# STM32.net
KiCad netlist of a schematic drawn in Altium Designer
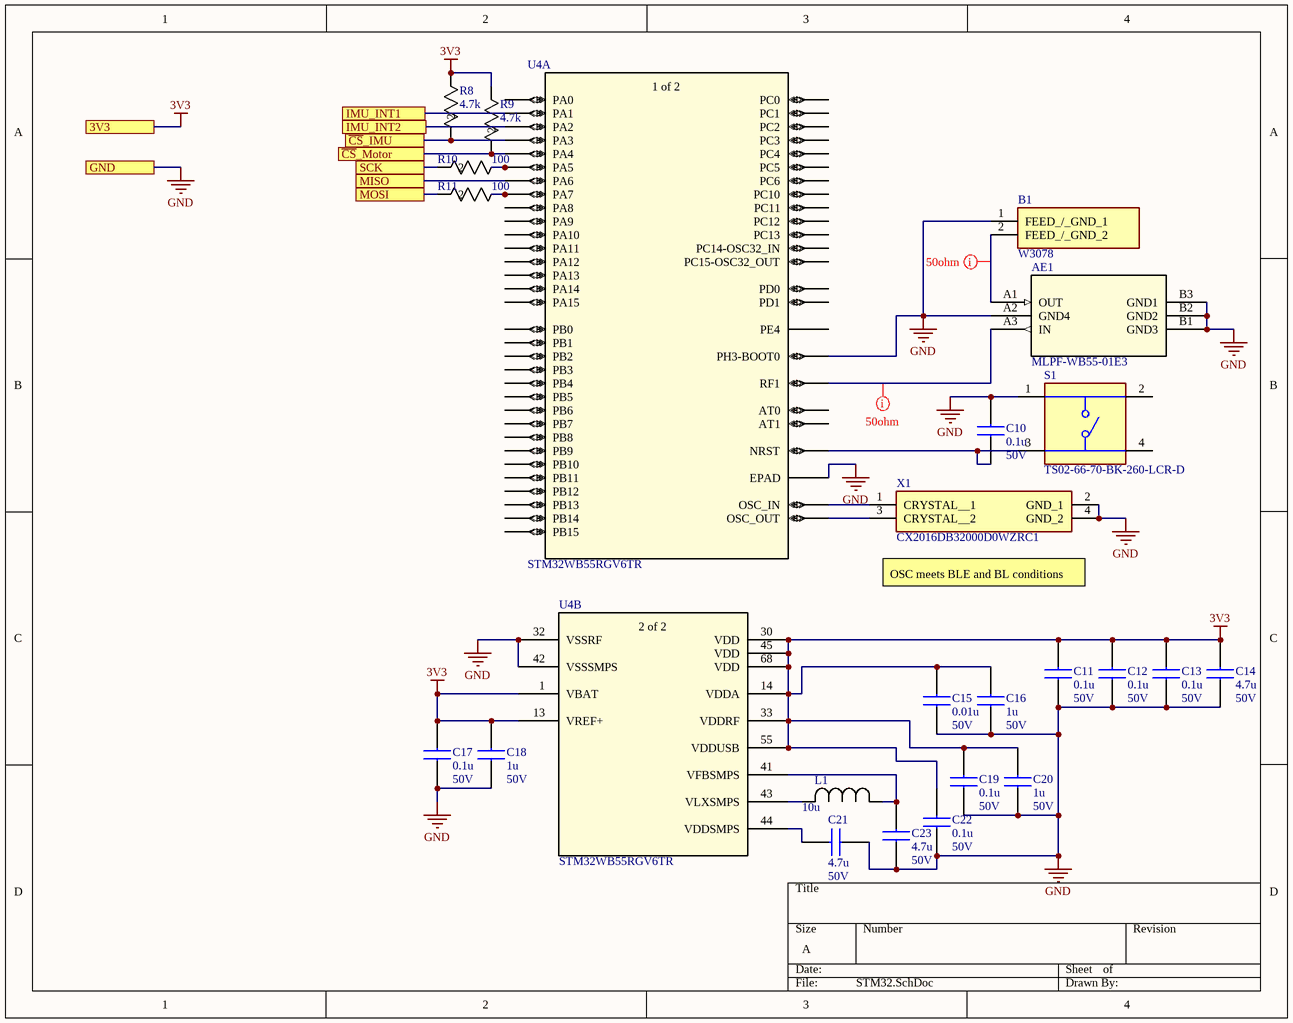
[diagram p0: STM32.SchDoc]

(export (version "E")
  (design (tool "Eeschema 10.0.6"))
  (components
    (comp (ref "AE1")
      (value "MLPF-WB55-01E3")
      (footprint "MLPF-WB55-01E3_STM")
      (description "2.4 GHz Matched filter companion chip for STM32WB55Cx and STM32WB55Rx")
      (fields (field (name "COPYRIGHT") "Copyright (C) 2025 Ultra Librarian. All rights reserved."))
      (libsource (lib "MLPF-WB55-01E3") (part "MLPF-WB55-01E3"))
    )
    (comp (ref "B1")
      (value "W3078")
      (footprint "W3078")
      (description "Antennas CERAMIC W3078 GC380H N")
      (fields (field (name "MOUSER PART NUMBER") "673-W3078"))
      (libsource (lib "W3078") (part "W3078"))
    )
    (comp (ref "C10")
      (value "0.1u")
      (footprint "CAPC2012X145N")
      (description "Multilayer Ceramic Chip Capacitors, Capacitance=0.1u")
      (fields
        (field (name "MANUFACTURER_PART_NUMBER") "KAM21BR71H104JM")
        (field (name "RATED VOLTAGE") "50V")
      )
      (libsource (lib "Caps") (part "KAM21BR71H104JM"))
    )
    (comp (ref "C11")
      (value "0.1u")
      (footprint "CAPC2012X145N")
      (description "Multilayer Ceramic Chip Capacitors, Capacitance=0.1u")
      (fields
        (field (name "MANUFACTURER_PART_NUMBER") "KAM21BR71H104JM")
        (field (name "RATED VOLTAGE") "50V")
      )
      (libsource (lib "Caps") (part "KAM21BR71H104JM"))
    )
    (comp (ref "C12")
      (value "0.1u")
      (footprint "CAPC2012X145N")
      (description "Multilayer Ceramic Chip Capacitors, Capacitance=0.1u")
      (fields
        (field (name "MANUFACTURER_PART_NUMBER") "KAM21BR71H104JM")
        (field (name "RATED VOLTAGE") "50V")
      )
      (libsource (lib "Caps") (part "KAM21BR71H104JM"))
    )
    (comp (ref "C13")
      (value "0.1u")
      (footprint "CAPC2012X145N")
      (description "Multilayer Ceramic Chip Capacitors, Capacitance=0.1u")
      (fields
        (field (name "MANUFACTURER_PART_NUMBER") "KAM21BR71H104JM")
        (field (name "RATED VOLTAGE") "50V")
      )
      (libsource (lib "Caps") (part "KAM21BR71H104JM"))
    )
    (comp (ref "C14")
      (value "4.7u")
      (footprint "CAPC2012X145N")
      (description "Multilayer Ceramic Chip Capacitors, Capacitance=4.7u")
      (fields
        (field (name "MANUFACTURER_PART_NUMBER") "GCM21BR71H474KA55K")
        (field (name "RATED VOLTAGE") "50V")
        (field (name "Comment") "C2012X5R1H475M125AB")
      )
      (libsource (lib "Caps") (part "C2012X5R1H475M125AB"))
    )
    (comp (ref "C15")
      (value "0.01u")
      (footprint "CAPC2012X145N")
      (description "Multilayer Ceramic Chip Capacitors, Capacitance=0.01u")
      (fields
        (field (name "MANUFACTURER_PART_NUMBER") "KAM21BR71H103KT")
        (field (name "RATED VOLTAGE") "50V")
      )
      (libsource (lib "Caps") (part "KAM21BR71H103KT"))
    )
    (comp (ref "C16")
      (value "1u")
      (footprint "CAPC2012X145N")
      (description "Multilayer Ceramic Chip Capacitors, Capacitance=1u")
      (fields
        (field (name "MANUFACTURER_PART_NUMBER") "KGM21AR51H105KU")
        (field (name "RATED VOLTAGE") "50V")
      )
      (libsource (lib "Caps") (part "KGM21AR51H105KU"))
    )
    (comp (ref "C17")
      (value "0.1u")
      (footprint "CAPC2012X145N")
      (description "Multilayer Ceramic Chip Capacitors, Capacitance=0.1u")
      (fields
        (field (name "MANUFACTURER_PART_NUMBER") "KAM21BR71H104JM")
        (field (name "RATED VOLTAGE") "50V")
      )
      (libsource (lib "Caps") (part "KAM21BR71H104JM"))
    )
    (comp (ref "C18")
      (value "1u")
      (footprint "CAPC2012X145N")
      (description "Multilayer Ceramic Chip Capacitors, Capacitance=1u")
      (fields
        (field (name "MANUFACTURER_PART_NUMBER") "KGM21AR51H105KU")
        (field (name "RATED VOLTAGE") "50V")
      )
      (libsource (lib "Caps") (part "KGM21AR51H105KU"))
    )
    (comp (ref "C19")
      (value "0.1u")
      (footprint "CAPC2012X145N")
      (description "Multilayer Ceramic Chip Capacitors, Capacitance=0.1u")
      (fields
        (field (name "MANUFACTURER_PART_NUMBER") "KAM21BR71H104JM")
        (field (name "RATED VOLTAGE") "50V")
      )
      (libsource (lib "Caps") (part "KAM21BR71H104JM"))
    )
    (comp (ref "C20")
      (value "1u")
      (footprint "CAPC2012X145N")
      (description "Multilayer Ceramic Chip Capacitors, Capacitance=1u")
      (fields
        (field (name "MANUFACTURER_PART_NUMBER") "KGM21AR51H105KU")
        (field (name "RATED VOLTAGE") "50V")
      )
      (libsource (lib "Caps") (part "KGM21AR51H105KU"))
    )
    (comp (ref "C21")
      (value "4.7u")
      (footprint "CAPC2012X145N")
      (description "Multilayer Ceramic Chip Capacitors, Capacitance=4.7u")
      (fields
        (field (name "MANUFACTURER_PART_NUMBER") "GCM21BR71H474KA55K")
        (field (name "RATED VOLTAGE") "50V")
        (field (name "Comment") "C2012X5R1H475M125AB")
      )
      (libsource (lib "Caps") (part "C2012X5R1H475M125AB"))
    )
    (comp (ref "C22")
      (value "0.1u")
      (footprint "CAPC2012X145N")
      (description "Multilayer Ceramic Chip Capacitors, Capacitance=0.1u")
      (fields
        (field (name "MANUFACTURER_PART_NUMBER") "KAM21BR71H104JM")
        (field (name "RATED VOLTAGE") "50V")
      )
      (libsource (lib "Caps") (part "KAM21BR71H104JM"))
    )
    (comp (ref "C23")
      (value "4.7u")
      (footprint "CAPC2012X145N")
      (description "Multilayer Ceramic Chip Capacitors, Capacitance=4.7u")
      (fields
        (field (name "MANUFACTURER_PART_NUMBER") "GCM21BR71H474KA55K")
        (field (name "RATED VOLTAGE") "50V")
        (field (name "Comment") "C2012X5R1H475M125AB")
      )
      (libsource (lib "Caps") (part "C2012X5R1H475M125AB"))
    )
    (comp (ref "L1")
      (value "10u")
      (footprint "IND_LQM21FN100M80L_MUR")
      (description "No Description Available")
      (fields
        (field (name "MANUFACTURER_PART_NUMBER") "LQM21FN100M80L")
        (field (name "COPYRIGHT") "Copyright (C) 2025 Ultra Librarian. All rights reserved.")
      )
      (libsource (lib "LQM21FN100M80L") (part "LQM21FN100M80L"))
    )
    (comp (ref "R8")
      (value "4.7k")
      (footprint "RC0805N_YAG")
      (description "RES 0805 4.7k 5% 1/8W")
      (fields (field (name "MANUFACTURER_PART_NUMBER") "RC0805JR-074K7L") (field (name "TOLERANCE") "5%"))
      (libsource (lib "Resistors") (part "RC0805JR-074K7L"))
    )
    (comp (ref "R9")
      (value "4.7k")
      (footprint "RC0805N_YAG")
      (description "RES 0805 4.7k 5% 1/8W")
      (fields (field (name "MANUFACTURER_PART_NUMBER") "RC0805JR-074K7L") (field (name "TOLERANCE") "5%"))
      (libsource (lib "Resistors") (part "RC0805JR-074K7L"))
    )
    (comp (ref "R10")
      (value "100")
      (footprint "RC0805N_YAG")
      (description "RES 0805 100 5% 1/8W")
      (fields (field (name "MANUFACTURER_PART_NUMBER") "RC0805JR-07100RL") (field (name "TOLERANCE") "5%"))
      (libsource (lib "Resistors") (part "RC0805JR-07100RL"))
    )
    (comp (ref "R11")
      (value "100")
      (footprint "RC0805N_YAG")
      (description "RES 0805 100 5% 1/8W")
      (fields (field (name "MANUFACTURER_PART_NUMBER") "RC0805JR-07100RL") (field (name "TOLERANCE") "5%"))
      (libsource (lib "Resistors") (part "RC0805JR-07100RL"))
    )
    (comp (ref "S1")
      (value "TS02-66-70-BK-260-LCR-D")
      (footprint "SW_TS02-66-70-BK-260-LCR-D")
      (description "6 x 6 mm, 7 mm Actuator Height, 260 gf, Black, Long Crimped, Through Hole, SPST, Tactile Switch")
      (fields (field (name "MF") "Same Sky"))
      (libsource (lib "TS02-66-70-BK-260-LCR-D") (part "TS02-66-70-BK-260-LCR-D"))
    )
    (comp (ref "U4")
      (value "STM32WB55RGV6TR")
      (footprint "VFQFN68-8x8mm")
      (fields (field (name "COPYRIGHT") "Copyright (C) 2025 Ultra Librarian. All rights reserved."))
      (libsource (lib "STM32WB55RGV6TR") (part "STM32WB55RGV6TR"))
    )
    (comp (ref "X1")
      (value "CX2016DB32000D0WZRC1")
      (footprint "CX2016DB32000D0WZRC1")
      (description "32 MHz +/-25ppm Crystal 8pF 60 Ohms 4-SMD, No Lead")
      (fields (field (name "MOUSER PART NUMBER") "581-CX2016DB32DWZRC1"))
      (libsource (lib "CX2016DB32000D0WZRC1") (part "CX2016DB32000D0WZRC1"))
    )
  )
  (nets
    (net (code "1") (name "/IMU_INT1") (class "Default")
      (node (ref "U4") (pin "16") (pinfunction "PA1_16") (pintype "bidirectional"))
    )
    (net (code "2") (name "/IMU_INT2") (class "Default")
      (node (ref "U4") (pin "17") (pinfunction "PA2_17") (pintype "bidirectional"))
    )
    (net (code "3") (name "/MISO") (class "Default")
      (node (ref "U4") (pin "21") (pinfunction "PA6_21") (pintype "bidirectional"))
    )
    (net (code "4") (name "/MOSI") (class "Default")
      (node (ref "R11") (pin "2") (pinfunction "2_2") (pintype "passive"))
    )
    (net (code "5") (name "/SCK") (class "Default")
      (node (ref "R10") (pin "2") (pinfunction "2_2") (pintype "passive"))
    )
    (net (code "6") (name "/~{CS}_IMU") (class "Default")
      (node (ref "R8") (pin "2") (pinfunction "2_2") (pintype "passive"))
      (node (ref "U4") (pin "18") (pinfunction "PA3_18") (pintype "bidirectional"))
    )
    (net (code "7") (name "/~{CS}_Motor") (class "Default")
      (node (ref "R9") (pin "2") (pinfunction "2_2") (pintype "passive"))
      (node (ref "U4") (pin "19") (pinfunction "PA4_19") (pintype "bidirectional"))
    )
    (net (code "8") (name "3V3") (class "Default")
      (node (ref "C11") (pin "2") (pinfunction "2_2") (pintype "passive"))
      (node (ref "C12") (pin "2") (pinfunction "2_2") (pintype "passive"))
      (node (ref "C13") (pin "2") (pinfunction "2_2") (pintype "passive"))
      (node (ref "C14") (pin "2") (pinfunction "2_2") (pintype "passive"))
      (node (ref "C15") (pin "2") (pinfunction "2_2") (pintype "passive"))
      (node (ref "C16") (pin "2") (pinfunction "2_2") (pintype "passive"))
      (node (ref "C17") (pin "2") (pinfunction "2_2") (pintype "passive"))
      (node (ref "C18") (pin "2") (pinfunction "2_2") (pintype "passive"))
      (node (ref "C19") (pin "2") (pinfunction "2_2") (pintype "passive"))
      (node (ref "C20") (pin "2") (pinfunction "2_2") (pintype "passive"))
      (node (ref "C22") (pin "2") (pinfunction "2_2") (pintype "passive"))
      (node (ref "R8") (pin "1") (pinfunction "1_1") (pintype "passive"))
      (node (ref "R9") (pin "1") (pinfunction "1_1") (pintype "passive"))
      (node (ref "U4") (pin "1") (pinfunction "VBAT_1") (pintype "power_in"))
      (node (ref "U4") (pin "13") (pinfunction "VREF+_13") (pintype "power_in"))
      (node (ref "U4") (pin "14") (pinfunction "VDDA_14") (pintype "power_in"))
      (node (ref "U4") (pin "30") (pinfunction "VDD_30") (pintype "power_in"))
      (node (ref "U4") (pin "33") (pinfunction "VDDRF_33") (pintype "power_in"))
      (node (ref "U4") (pin "45") (pinfunction "VDD_45") (pintype "power_in"))
      (node (ref "U4") (pin "55") (pinfunction "VDDUSB_55") (pintype "power_in"))
      (node (ref "U4") (pin "68") (pinfunction "VDD_68") (pintype "power_in"))
    )
    (net (code "9") (name "GND") (class "Default")
      (node (ref "AE1") (pin "A2") (pinfunction "GND4_A2") (pintype "power_in"))
      (node (ref "AE1") (pin "B1") (pinfunction "GND3_B1") (pintype "power_in"))
      (node (ref "AE1") (pin "B2") (pinfunction "GND2_B2") (pintype "power_in"))
      (node (ref "AE1") (pin "B3") (pinfunction "GND1_B3") (pintype "power_in"))
      (node (ref "B1") (pin "1") (pinfunction "FEED_/_GND_1_1") (pintype "passive"))
      (node (ref "C10") (pin "2") (pinfunction "2_2") (pintype "passive"))
      (node (ref "C11") (pin "1") (pinfunction "1_1") (pintype "passive"))
      (node (ref "C12") (pin "1") (pinfunction "1_1") (pintype "passive"))
      (node (ref "C13") (pin "1") (pinfunction "1_1") (pintype "passive"))
      (node (ref "C14") (pin "1") (pinfunction "1_1") (pintype "passive"))
      (node (ref "C15") (pin "1") (pinfunction "1_1") (pintype "passive"))
      (node (ref "C16") (pin "1") (pinfunction "1_1") (pintype "passive"))
      (node (ref "C17") (pin "1") (pinfunction "1_1") (pintype "passive"))
      (node (ref "C18") (pin "1") (pinfunction "1_1") (pintype "passive"))
      (node (ref "C19") (pin "1") (pinfunction "1_1") (pintype "passive"))
      (node (ref "C20") (pin "1") (pinfunction "1_1") (pintype "passive"))
      (node (ref "C21") (pin "1") (pinfunction "1_1") (pintype "passive"))
      (node (ref "C22") (pin "1") (pinfunction "1_1") (pintype "passive"))
      (node (ref "C23") (pin "1") (pinfunction "1_1") (pintype "passive"))
      (node (ref "S1") (pin "1") (pinfunction "1_1") (pintype "passive"))
      (node (ref "U4") (pin "32") (pinfunction "VSSRF_32") (pintype "power_in"))
      (node (ref "U4") (pin "42") (pinfunction "VSSSMPS_42") (pintype "power_in"))
      (node (ref "U4") (pin "5") (pinfunction "PH3-BOOT0_5") (pintype "bidirectional"))
      (node (ref "U4") (pin "69") (pinfunction "EPAD_69") (pintype "passive"))
      (node (ref "X1") (pin "2") (pinfunction "GND_1_2") (pintype "passive"))
      (node (ref "X1") (pin "4") (pinfunction "GND_2_4") (pintype "passive"))
    )
    (net (code "10") (name "Net-(AE1-IN)") (class "Default")
      (node (ref "AE1") (pin "A3") (pinfunction "IN_A3") (pintype "output"))
      (node (ref "U4") (pin "31") (pinfunction "RF1_31") (pintype "bidirectional"))
    )
    (net (code "11") (name "Net-(AE1-OUT)") (class "Default")
      (node (ref "AE1") (pin "A1") (pinfunction "OUT_A1") (pintype "input"))
      (node (ref "B1") (pin "2") (pinfunction "FEED_/_GND_2_2") (pintype "passive"))
    )
    (net (code "12") (name "Net-(U4A-NRST)") (class "Default")
      (node (ref "C10") (pin "1") (pinfunction "1_1") (pintype "passive"))
      (node (ref "S1") (pin "3") (pinfunction "3_3") (pintype "passive"))
      (node (ref "U4") (pin "8") (pinfunction "NRST_8") (pintype "bidirectional"))
    )
    (net (code "13") (name "Net-(U4A-OSC_IN)") (class "Default")
      (node (ref "U4") (pin "35") (pinfunction "OSC_IN_35") (pintype "bidirectional"))
      (node (ref "X1") (pin "1") (pinfunction "CRYSTAL__1_1") (pintype "passive"))
    )
    (net (code "14") (name "Net-(U4A-OSC_OUT)") (class "Default")
      (node (ref "U4") (pin "34") (pinfunction "OSC_OUT_34") (pintype "bidirectional"))
      (node (ref "X1") (pin "3") (pinfunction "CRYSTAL__2_3") (pintype "passive"))
    )
    (net (code "15") (name "Net-(U4A-PA5)") (class "Default")
      (node (ref "R10") (pin "1") (pinfunction "1_1") (pintype "passive"))
      (node (ref "U4") (pin "20") (pinfunction "PA5_20") (pintype "bidirectional"))
    )
    (net (code "16") (name "Net-(U4A-PA7)") (class "Default")
      (node (ref "R11") (pin "1") (pinfunction "1_1") (pintype "passive"))
      (node (ref "U4") (pin "22") (pinfunction "PA7_22") (pintype "bidirectional"))
    )
    (net (code "17") (name "Net-(U4B-VDDSMPS)") (class "Default")
      (node (ref "C21") (pin "2") (pinfunction "2_2") (pintype "passive"))
      (node (ref "U4") (pin "44") (pinfunction "VDDSMPS_44") (pintype "power_in"))
    )
    (net (code "18") (name "Net-(U4B-VFBSMPS)") (class "Default")
      (node (ref "C23") (pin "2") (pinfunction "2_2") (pintype "passive"))
      (node (ref "L1") (pin "1") (pinfunction "1_1") (pintype "passive"))
      (node (ref "U4") (pin "41") (pinfunction "VFBSMPS_41") (pintype "power_in"))
    )
    (net (code "19") (name "Net-(U4B-VLXSMPS)") (class "Default")
      (node (ref "L1") (pin "2") (pinfunction "2_2") (pintype "passive"))
      (node (ref "U4") (pin "43") (pinfunction "VLXSMPS_43") (pintype "power_in"))
    )
    (net (code "20") (name "unconnected-(S1-Pad2)") (class "Default")
      (node (ref "S1") (pin "2") (pinfunction "2_2") (pintype "passive"))
    )
    (net (code "21") (name "unconnected-(S1-Pad4)") (class "Default")
      (node (ref "S1") (pin "4") (pinfunction "4_4") (pintype "passive"))
    )
    (net (code "22") (name "unconnected-(U4A-AT0-Pad36)") (class "Default")
      (node (ref "U4") (pin "36") (pinfunction "AT0_36") (pintype "bidirectional"))
    )
    (net (code "23") (name "unconnected-(U4A-AT1-Pad37)") (class "Default")
      (node (ref "U4") (pin "37") (pinfunction "AT1_37") (pintype "bidirectional"))
    )
    (net (code "24") (name "unconnected-(U4A-PA0-Pad15)") (class "Default")
      (node (ref "U4") (pin "15") (pinfunction "PA0_15") (pintype "bidirectional"))
    )
    (net (code "25") (name "unconnected-(U4A-PA8-Pad23)") (class "Default")
      (node (ref "U4") (pin "23") (pinfunction "PA8_23") (pintype "bidirectional"))
    )
    (net (code "26") (name "unconnected-(U4A-PA9-Pad24)") (class "Default")
      (node (ref "U4") (pin "24") (pinfunction "PA9_24") (pintype "bidirectional"))
    )
    (net (code "27") (name "unconnected-(U4A-PA10-Pad51)") (class "Default")
      (node (ref "U4") (pin "51") (pinfunction "PA10_51") (pintype "bidirectional"))
    )
    (net (code "28") (name "unconnected-(U4A-PA11-Pad52)") (class "Default")
      (node (ref "U4") (pin "52") (pinfunction "PA11_52") (pintype "bidirectional"))
    )
    (net (code "29") (name "unconnected-(U4A-PA12-Pad53)") (class "Default")
      (node (ref "U4") (pin "53") (pinfunction "PA12_53") (pintype "bidirectional"))
    )
    (net (code "30") (name "unconnected-(U4A-PA13-Pad54)") (class "Default")
      (node (ref "U4") (pin "54") (pinfunction "PA13_54") (pintype "bidirectional"))
    )
    (net (code "31") (name "unconnected-(U4A-PA14-Pad56)") (class "Default")
      (node (ref "U4") (pin "56") (pinfunction "PA14_56") (pintype "bidirectional"))
    )
    (net (code "32") (name "unconnected-(U4A-PA15-Pad57)") (class "Default")
      (node (ref "U4") (pin "57") (pinfunction "PA15_57") (pintype "bidirectional"))
    )
    (net (code "33") (name "unconnected-(U4A-PB0-Pad38)") (class "Default")
      (node (ref "U4") (pin "38") (pinfunction "PB0_38") (pintype "bidirectional"))
    )
    (net (code "34") (name "unconnected-(U4A-PB1-Pad39)") (class "Default")
      (node (ref "U4") (pin "39") (pinfunction "PB1_39") (pintype "bidirectional"))
    )
    (net (code "35") (name "unconnected-(U4A-PB2-Pad27)") (class "Default")
      (node (ref "U4") (pin "27") (pinfunction "PB2_27") (pintype "bidirectional"))
    )
    (net (code "36") (name "unconnected-(U4A-PB3-Pad63)") (class "Default")
      (node (ref "U4") (pin "63") (pinfunction "PB3_63") (pintype "bidirectional"))
    )
    (net (code "37") (name "unconnected-(U4A-PB4-Pad64)") (class "Default")
      (node (ref "U4") (pin "64") (pinfunction "PB4_64") (pintype "bidirectional"))
    )
    (net (code "38") (name "unconnected-(U4A-PB5-Pad65)") (class "Default")
      (node (ref "U4") (pin "65") (pinfunction "PB5_65") (pintype "bidirectional"))
    )
    (net (code "39") (name "unconnected-(U4A-PB6-Pad66)") (class "Default")
      (node (ref "U4") (pin "66") (pinfunction "PB6_66") (pintype "bidirectional"))
    )
    (net (code "40") (name "unconnected-(U4A-PB7-Pad67)") (class "Default")
      (node (ref "U4") (pin "67") (pinfunction "PB7_67") (pintype "bidirectional"))
    )
    (net (code "41") (name "unconnected-(U4A-PB8-Pad6)") (class "Default")
      (node (ref "U4") (pin "6") (pinfunction "PB8_6") (pintype "bidirectional"))
    )
    (net (code "42") (name "unconnected-(U4A-PB9-Pad7)") (class "Default")
      (node (ref "U4") (pin "7") (pinfunction "PB9_7") (pintype "bidirectional"))
    )
    (net (code "43") (name "unconnected-(U4A-PB10-Pad28)") (class "Default")
      (node (ref "U4") (pin "28") (pinfunction "PB10_28") (pintype "bidirectional"))
    )
    (net (code "44") (name "unconnected-(U4A-PB11-Pad29)") (class "Default")
      (node (ref "U4") (pin "29") (pinfunction "PB11_29") (pintype "bidirectional"))
    )
    (net (code "45") (name "unconnected-(U4A-PB12-Pad46)") (class "Default")
      (node (ref "U4") (pin "46") (pinfunction "PB12_46") (pintype "bidirectional"))
    )
    (net (code "46") (name "unconnected-(U4A-PB13-Pad47)") (class "Default")
      (node (ref "U4") (pin "47") (pinfunction "PB13_47") (pintype "bidirectional"))
    )
    (net (code "47") (name "unconnected-(U4A-PB14-Pad48)") (class "Default")
      (node (ref "U4") (pin "48") (pinfunction "PB14_48") (pintype "bidirectional"))
    )
    (net (code "48") (name "unconnected-(U4A-PB15-Pad49)") (class "Default")
      (node (ref "U4") (pin "49") (pinfunction "PB15_49") (pintype "bidirectional"))
    )
    (net (code "49") (name "unconnected-(U4A-PC0-Pad9)") (class "Default")
      (node (ref "U4") (pin "9") (pinfunction "PC0_9") (pintype "bidirectional"))
    )
    (net (code "50") (name "unconnected-(U4A-PC1-Pad10)") (class "Default")
      (node (ref "U4") (pin "10") (pinfunction "PC1_10") (pintype "bidirectional"))
    )
    (net (code "51") (name "unconnected-(U4A-PC2-Pad11)") (class "Default")
      (node (ref "U4") (pin "11") (pinfunction "PC2_11") (pintype "bidirectional"))
    )
    (net (code "52") (name "unconnected-(U4A-PC3-Pad12)") (class "Default")
      (node (ref "U4") (pin "12") (pinfunction "PC3_12") (pintype "bidirectional"))
    )
    (net (code "53") (name "unconnected-(U4A-PC4-Pad25)") (class "Default")
      (node (ref "U4") (pin "25") (pinfunction "PC4_25") (pintype "bidirectional"))
    )
    (net (code "54") (name "unconnected-(U4A-PC5-Pad26)") (class "Default")
      (node (ref "U4") (pin "26") (pinfunction "PC5_26") (pintype "bidirectional"))
    )
    (net (code "55") (name "unconnected-(U4A-PC6-Pad50)") (class "Default")
      (node (ref "U4") (pin "50") (pinfunction "PC6_50") (pintype "bidirectional"))
    )
    (net (code "56") (name "unconnected-(U4A-PC10-Pad58)") (class "Default")
      (node (ref "U4") (pin "58") (pinfunction "PC10_58") (pintype "bidirectional"))
    )
    (net (code "57") (name "unconnected-(U4A-PC11-Pad59)") (class "Default")
      (node (ref "U4") (pin "59") (pinfunction "PC11_59") (pintype "bidirectional"))
    )
    (net (code "58") (name "unconnected-(U4A-PC12-Pad60)") (class "Default")
      (node (ref "U4") (pin "60") (pinfunction "PC12_60") (pintype "bidirectional"))
    )
    (net (code "59") (name "unconnected-(U4A-PC13-Pad2)") (class "Default")
      (node (ref "U4") (pin "2") (pinfunction "PC13_2") (pintype "bidirectional"))
    )
    (net (code "60") (name "unconnected-(U4A-PC14-OSC32_IN-Pad3)") (class "Default")
      (node (ref "U4") (pin "3") (pinfunction "PC14-OSC32_IN_3") (pintype "bidirectional"))
    )
    (net (code "61") (name "unconnected-(U4A-PC15-OSC32_OUT-Pad4)") (class "Default")
      (node (ref "U4") (pin "4") (pinfunction "PC15-OSC32_OUT_4") (pintype "bidirectional"))
    )
    (net (code "62") (name "unconnected-(U4A-PD0-Pad61)") (class "Default")
      (node (ref "U4") (pin "61") (pinfunction "PD0_61") (pintype "bidirectional"))
    )
    (net (code "63") (name "unconnected-(U4A-PD1-Pad62)") (class "Default")
      (node (ref "U4") (pin "62") (pinfunction "PD1_62") (pintype "bidirectional"))
    )
    (net (code "64") (name "unconnected-(U4A-PE4-Pad40)") (class "Default")
      (node (ref "U4") (pin "40") (pinfunction "PE4_40") (pintype "power_in"))
    )
  )
)
